# OpenPLCv0_2_0_RTC.net
KiCad netlist of a schematic drawn in Altium Designer
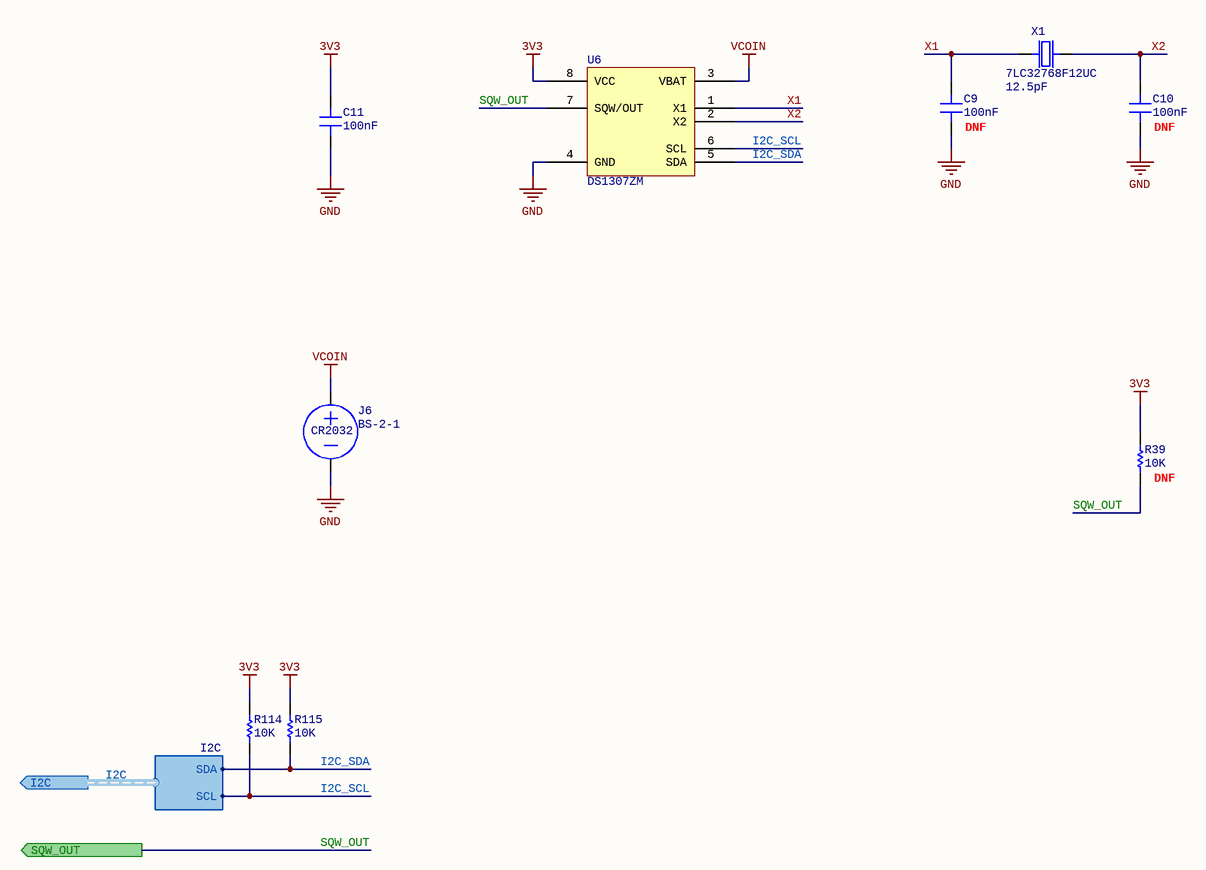
[diagram p0: OpenPLCv0.2.0_RTC.SchDoc]

(export (version "E")
  (design (tool "Eeschema 10.0.6"))
  (components
    (comp (ref "C9")
      (value "CC0402KRX5R9BB104")
      (footprint "SMD_CAP_0402(1005)_N")
      (description "100nF ±10% 50V X5R 0402 Multilayer Ceramic Capacitors MLCC - SMD/SMT RoHS")
      (fields (field (name "TOLERANCE") "10%") (field (name "CAPACITANCE") "100nF"))
      (libsource (lib "*") (part "100nF 0402 50V 10%"))
    )
    (comp (ref "C10")
      (value "CC0402KRX5R9BB104")
      (footprint "SMD_CAP_0402(1005)_N")
      (description "100nF ±10% 50V X5R 0402 Multilayer Ceramic Capacitors MLCC - SMD/SMT RoHS")
      (fields (field (name "TOLERANCE") "10%") (field (name "CAPACITANCE") "100nF"))
      (libsource (lib "*") (part "100nF 0402 50V 10%"))
    )
    (comp (ref "C11")
      (value "CC0402KRX5R6BB104")
      (footprint "SMD_CAP_0402(1005)_N")
      (description "100nF ±10% 10V X5R 0402 Multilayer Ceramic Capacitors MLCC - SMD/SMT RoHS")
      (fields (field (name "TOLERANCE") "10%") (field (name "CAPACITANCE") "100nF"))
      (libsource (lib "BrauV2_Capacitor") (part "100nF 0402 10V 10%"))
    )
    (comp (ref "J6")
      (value "BS-2-1")
      (footprint "BS-2-1")
      (description "DIP Battery Box/Battery Holders ROHS")
      (libsource (lib "OpenPLCv0.2.0_Connector") (part "BS-2-1"))
    )
    (comp (ref "R39")
      (value "RC0402FR-0710KL")
      (footprint "SMD_RES_0402(1005)_N")
      (description "10kΩ ±1% 1/16W ±100ppm/℃ 0402 Chip Resistor - Surface Mount RoHS")
      (fields (field (name "TOLERANCE") "1%") (field (name "RESISTANCE") "10K"))
      (libsource (lib "BrauV2_Resistor") (part "10K 0402 1% 1/16W"))
    )
    (comp (ref "R114")
      (value "RC0402FR-0710KL")
      (footprint "SMD_RES_0402(1005)_N")
      (description "10kΩ ±1% 1/16W ±100ppm/℃ 0402 Chip Resistor - Surface Mount RoHS")
      (fields (field (name "TOLERANCE") "1%") (field (name "RESISTANCE") "10K"))
      (libsource (lib "BrauV2_Resistor") (part "10K 0402 1% 1/16W"))
    )
    (comp (ref "R115")
      (value "RC0402FR-0710KL")
      (footprint "SMD_RES_0402(1005)_N")
      (description "10kΩ ±1% 1/16W ±100ppm/℃ 0402 Chip Resistor - Surface Mount RoHS")
      (fields (field (name "TOLERANCE") "1%") (field (name "RESISTANCE") "10K"))
      (libsource (lib "BrauV2_Resistor") (part "10K 0402 1% 1/16W"))
    )
    (comp (ref "U6")
      (value "DS1307ZM")
      (footprint "SOIC-8-3.9mm")
      (description "HGSEMI SOP-8 Pre-ordered Chips RoHS")
      (libsource (lib "BrauV2_IC") (part "DS1307ZM"))
    )
    (comp (ref "X1")
      (value "7LC32768F12UC")
      (footprint "CRYSTAL_3215")
      (description "32.768KHz ±20ppm 12.5pF 70kΩ SMD-3215_2P SMD Crystal Resonators RoHS")
      (fields (field (name "LOAD CAPACITANCE") "12.5pF"))
      (libsource (lib "BrauV2_Passives") (part "7LC32768F12UC"))
    )
  )
  (nets
    (net (code "2") (name "/I2C_SCL") (class "Default")
      (node (ref "R114") (pin "1") (pinfunction "1_1") (pintype "passive"))
      (node (ref "U6") (pin "6") (pinfunction "SCL_6") (pintype "passive"))
    )
    (net (code "3") (name "/I2C_SDA") (class "Default")
      (node (ref "R115") (pin "1") (pinfunction "1_1") (pintype "passive"))
      (node (ref "U6") (pin "5") (pinfunction "SDA_5") (pintype "passive"))
    )
    (net (code "5") (name "/SQW_OUT") (class "Default")
      (node (ref "R39") (pin "2") (pinfunction "2_2") (pintype "passive"))
      (node (ref "U6") (pin "7") (pinfunction "SQW/OUT_7") (pintype "passive"))
    )
    (net (code "6") (name "/X1") (class "Default")
      (node (ref "C9") (pin "2") (pinfunction "2_2") (pintype "passive"))
      (node (ref "U6") (pin "1") (pinfunction "X1_1") (pintype "passive"))
      (node (ref "X1") (pin "1") (pinfunction "1_1") (pintype "passive"))
    )
    (net (code "7") (name "/X2") (class "Default")
      (node (ref "C10") (pin "2") (pinfunction "2_2") (pintype "passive"))
      (node (ref "U6") (pin "2") (pinfunction "X2_2") (pintype "passive"))
      (node (ref "X1") (pin "2") (pinfunction "2_2") (pintype "passive"))
    )
    (net (code "8") (name "3V3") (class "Default")
      (node (ref "C11") (pin "2") (pinfunction "2_2") (pintype "passive"))
      (node (ref "R114") (pin "2") (pinfunction "2_2") (pintype "passive"))
      (node (ref "R115") (pin "2") (pinfunction "2_2") (pintype "passive"))
      (node (ref "R39") (pin "1") (pinfunction "1_1") (pintype "passive"))
      (node (ref "U6") (pin "8") (pinfunction "VCC_8") (pintype "passive"))
    )
    (net (code "9") (name "GND") (class "Default")
      (node (ref "C10") (pin "1") (pinfunction "1_1") (pintype "passive"))
      (node (ref "C11") (pin "1") (pinfunction "1_1") (pintype "passive"))
      (node (ref "C9") (pin "1") (pinfunction "1_1") (pintype "passive"))
      (node (ref "J6") (pin "2") (pinfunction "2_2") (pintype "passive"))
      (node (ref "U6") (pin "4") (pinfunction "GND_4") (pintype "passive"))
    )
    (net (code "10") (name "VCOIN") (class "Default")
      (node (ref "J6") (pin "1") (pinfunction "1_1") (pintype "passive"))
      (node (ref "U6") (pin "3") (pinfunction "VBAT_3") (pintype "passive"))
    )
  )
)
